# tiny-ws2812b.net
KiCad netlist of a schematic drawn in EAGLE
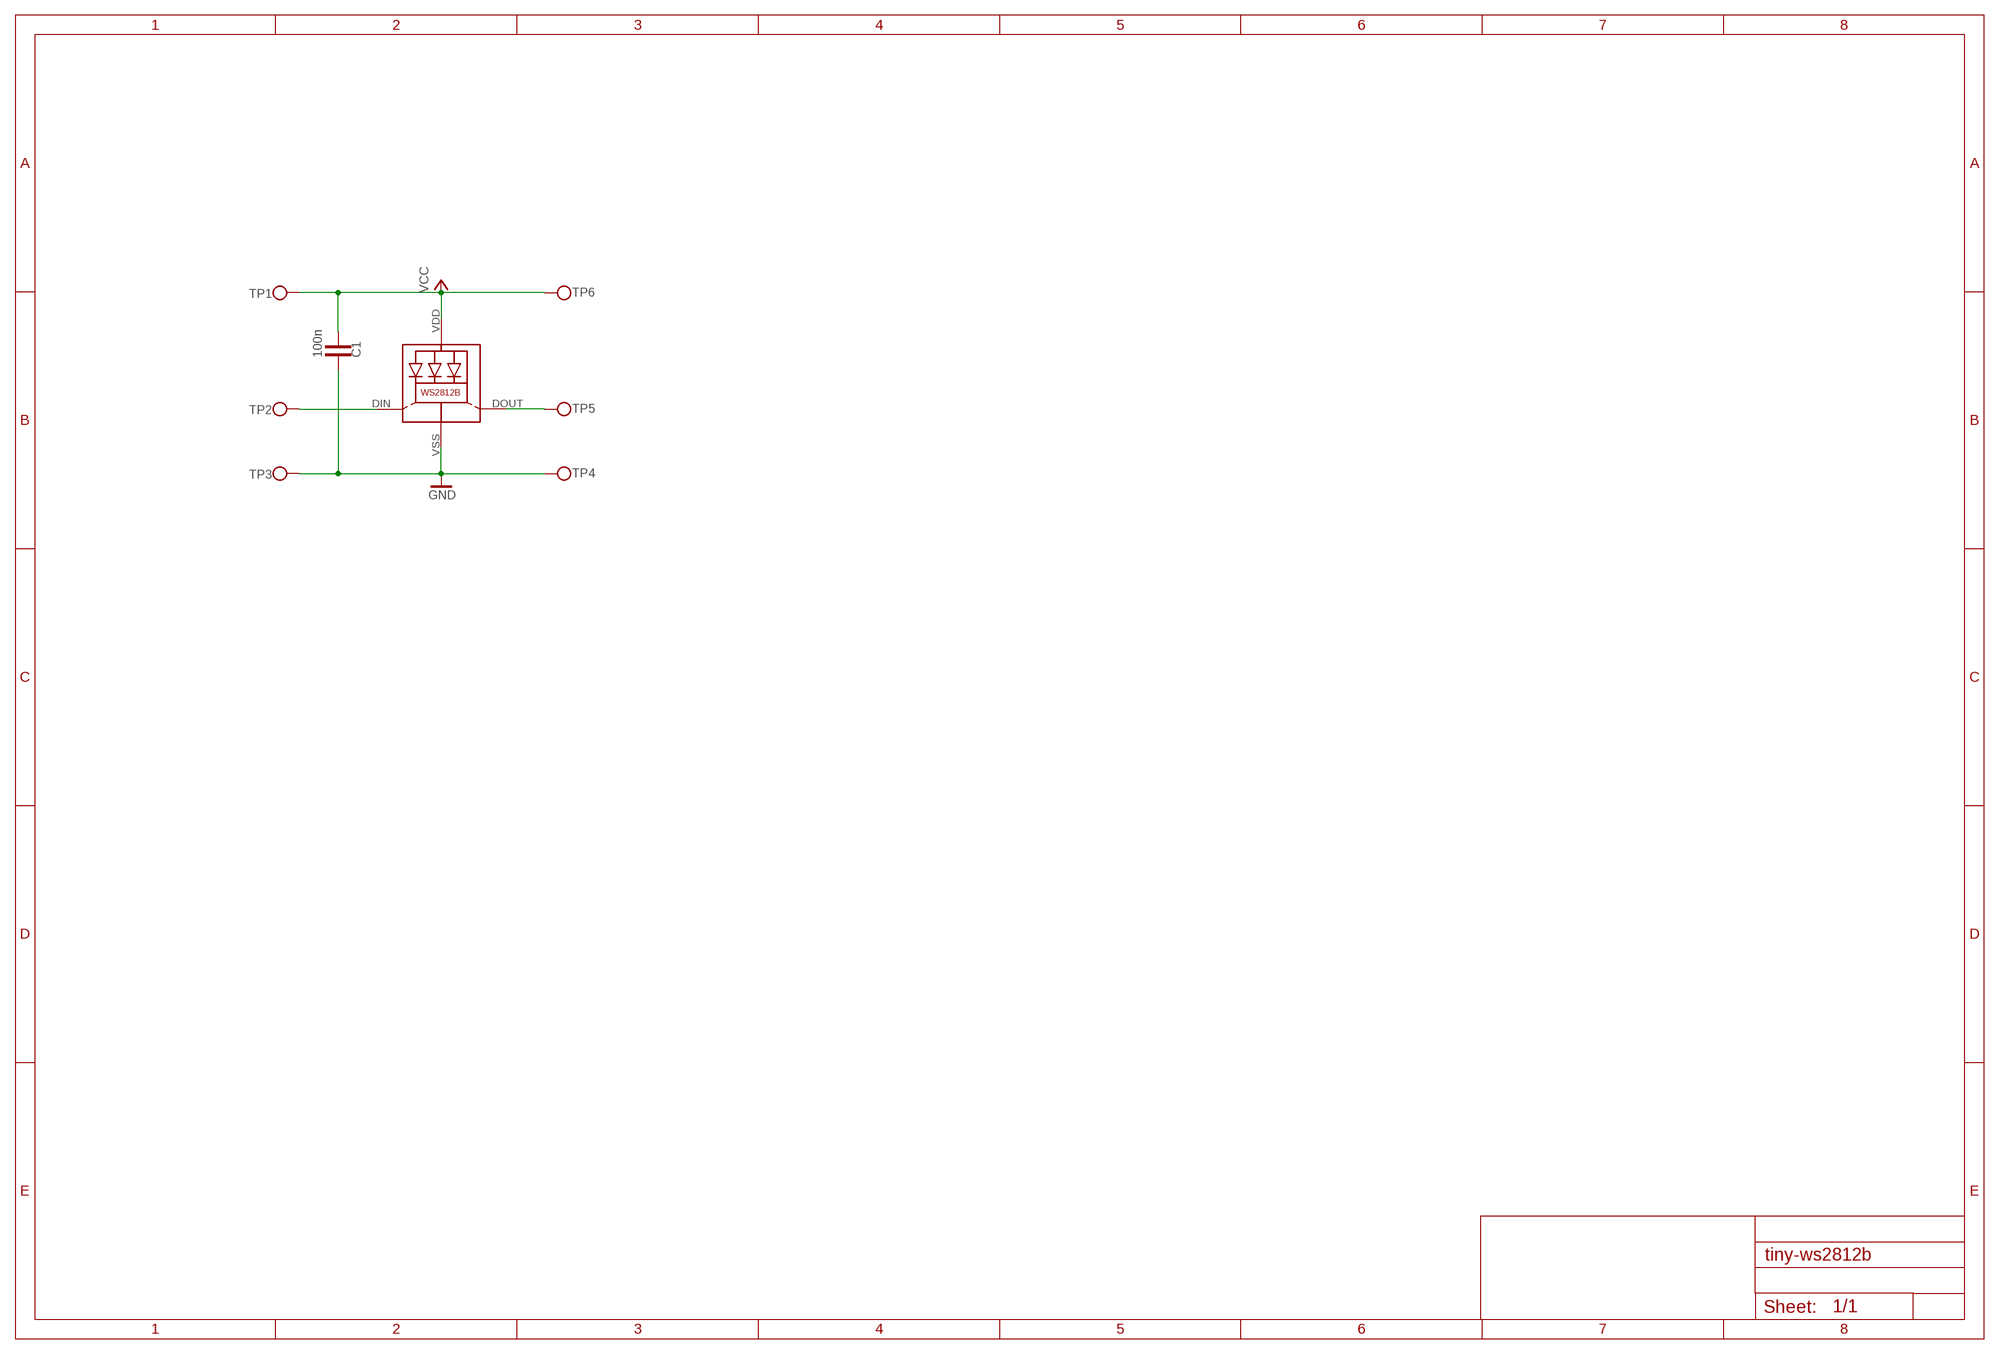
[diagram p0: schematic, sheet 1]

(export (version "E")
  (design (tool "Eeschema 10.0.6"))
  (components
    (comp (ref "C1")
      (value "100n")
      (footprint "eagle-import:0603MIL")
      (libsource (lib "eagle-import") (part "C0603"))
    )
    (comp (ref "LED1")
      (value "WS2812B")
      (footprint "eagle-import:WS2812B")
      (libsource (lib "eagle-import") (part "WS2812B"))
    )
    (comp (ref "TP1")
      (value "TP_Q2X1MM")
      (footprint "eagle-import:PAD_Q2X1MM")
      (libsource (lib "eagle-import") (part "TP_Q2X1MM"))
    )
    (comp (ref "TP2")
      (value "TP_Q2X1MM")
      (footprint "eagle-import:PAD_Q2X1MM")
      (libsource (lib "eagle-import") (part "TP_Q2X1MM"))
    )
    (comp (ref "TP3")
      (value "TP_Q2X1MM")
      (footprint "eagle-import:PAD_Q2X1MM")
      (libsource (lib "eagle-import") (part "TP_Q2X1MM"))
    )
    (comp (ref "TP4")
      (value "TP_Q2X1MM")
      (footprint "eagle-import:PAD_Q2X1MM")
      (libsource (lib "eagle-import") (part "TP_Q2X1MM"))
    )
    (comp (ref "TP5")
      (value "TP_Q2X1MM")
      (footprint "eagle-import:PAD_Q2X1MM")
      (libsource (lib "eagle-import") (part "TP_Q2X1MM"))
    )
    (comp (ref "TP6")
      (value "TP_Q2X1MM")
      (footprint "eagle-import:PAD_Q2X1MM")
      (libsource (lib "eagle-import") (part "TP_Q2X1MM"))
    )
  )
  (nets
    (net (code "1") (name "GND") (class "Default")
      (node (ref "C1") (pin "1") (pinfunction "1_1") (pintype "passive"))
      (node (ref "LED1") (pin "VSS") (pinfunction "GND_VSS") (pintype "power_in"))
      (node (ref "TP3") (pin "1") (pinfunction "P$1_1") (pintype "bidirectional"))
      (node (ref "TP4") (pin "1") (pinfunction "P$1_1") (pintype "bidirectional"))
    )
    (net (code "2") (name "Net-(LED1-DI)") (class "Default")
      (node (ref "LED1") (pin "DIN") (pinfunction "DI_DIN") (pintype "input"))
      (node (ref "TP2") (pin "1") (pinfunction "P$1_1") (pintype "bidirectional"))
    )
    (net (code "3") (name "Net-(LED1-DO)") (class "Default")
      (node (ref "LED1") (pin "DOUT") (pinfunction "DO_DOUT") (pintype "output"))
      (node (ref "TP5") (pin "1") (pinfunction "P$1_1") (pintype "bidirectional"))
    )
    (net (code "4") (name "VCC") (class "Default")
      (node (ref "C1") (pin "2") (pinfunction "2_2") (pintype "passive"))
      (node (ref "LED1") (pin "VDD") (pinfunction "VDD_VDD") (pintype "power_in"))
      (node (ref "TP1") (pin "1") (pinfunction "P$1_1") (pintype "bidirectional"))
      (node (ref "TP6") (pin "1") (pinfunction "P$1_1") (pintype "bidirectional"))
    )
  )
)
